# STM32G473CET6_PINOUT.net
KiCad netlist of a schematic drawn in Altium Designer
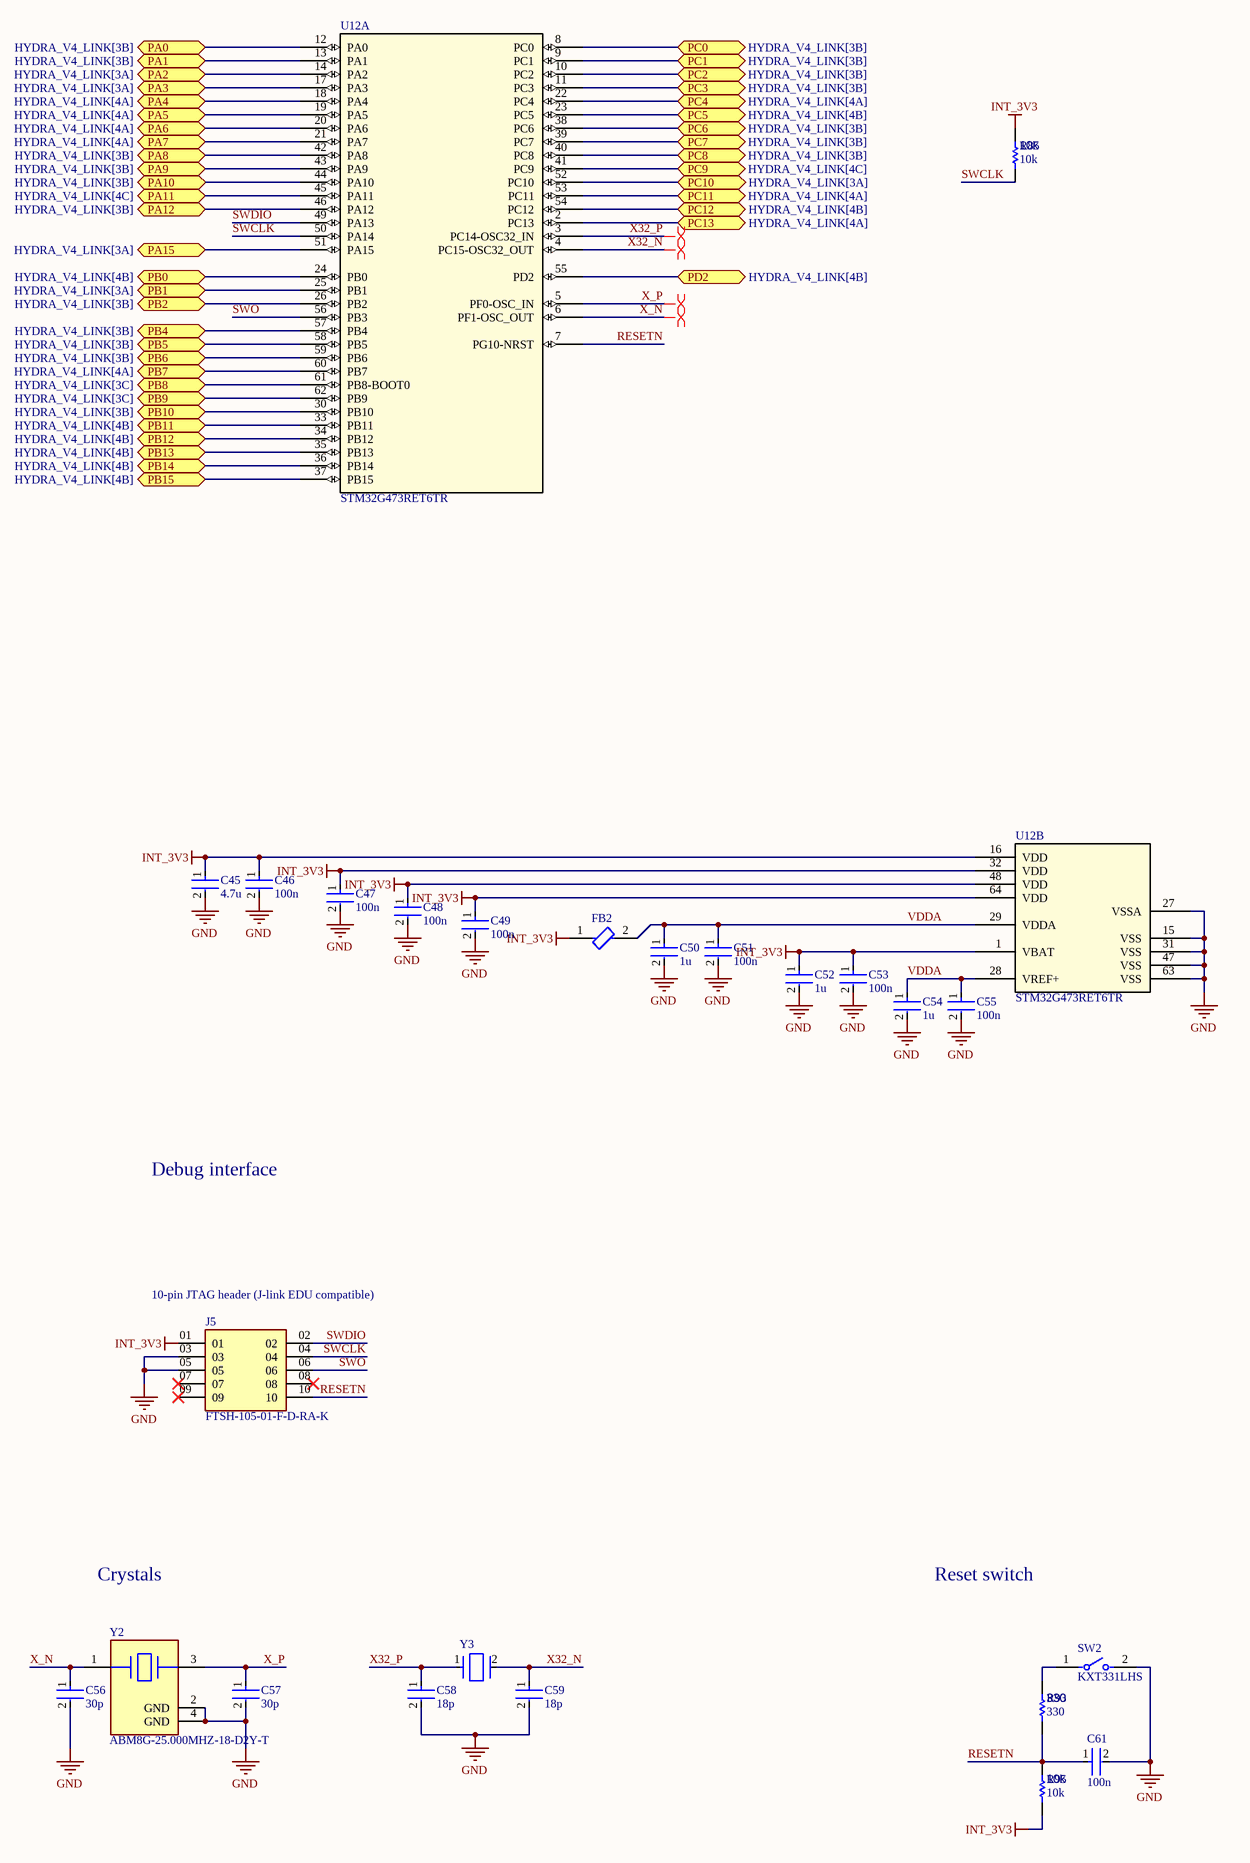
[diagram p0: STM32G473CET6_PINOUT.SchDoc]

(export (version "E")
  (design (tool "Eeschema 10.0.6"))
  (components
    (comp (ref "C45")
      (value "4.7u")
      (footprint "FP-0402-L_1_0_0_05-W_0_5-IPC_A")
      (description "LARGE PADS, 0402 CAP, CHANGE COMMENT TO MATCH REAL P/N")
      (libsource (lib "Space Concordia") (part "b4654b650e69147ec39a6b967a45e02"))
    )
    (comp (ref "C46")
      (value "100n")
      (footprint "FP-0402-L_1_0_0_05-W_0_5-IPC_A")
      (description "LARGE PADS, 0402 CAP, CHANGE COMMENT TO MATCH REAL P/N")
      (libsource (lib "Space Concordia") (part "b4654b650e69147ec39a6b967a45e02"))
    )
    (comp (ref "C47")
      (value "100n")
      (footprint "FP-0402-L_1_0_0_05-W_0_5-IPC_A")
      (description "LARGE PADS, 0402 CAP, CHANGE COMMENT TO MATCH REAL P/N")
      (libsource (lib "Space Concordia") (part "b4654b650e69147ec39a6b967a45e02"))
    )
    (comp (ref "C48")
      (value "100n")
      (footprint "FP-0402-L_1_0_0_05-W_0_5-IPC_A")
      (description "LARGE PADS, 0402 CAP, CHANGE COMMENT TO MATCH REAL P/N")
      (libsource (lib "Space Concordia") (part "b4654b650e69147ec39a6b967a45e02"))
    )
    (comp (ref "C49")
      (value "100n")
      (footprint "FP-0402-L_1_0_0_05-W_0_5-IPC_A")
      (description "LARGE PADS, 0402 CAP, CHANGE COMMENT TO MATCH REAL P/N")
      (libsource (lib "Space Concordia") (part "b4654b650e69147ec39a6b967a45e02"))
    )
    (comp (ref "C50")
      (value "1u")
      (footprint "FP-0402-L_1_0_0_05-W_0_5-IPC_A")
      (description "LARGE PADS, 0402 CAP, CHANGE COMMENT TO MATCH REAL P/N")
      (libsource (lib "Space Concordia") (part "b4654b650e69147ec39a6b967a45e02"))
    )
    (comp (ref "C51")
      (value "100n")
      (footprint "FP-0402-L_1_0_0_05-W_0_5-IPC_A")
      (description "LARGE PADS, 0402 CAP, CHANGE COMMENT TO MATCH REAL P/N")
      (libsource (lib "Space Concordia") (part "b4654b650e69147ec39a6b967a45e02"))
    )
    (comp (ref "C52")
      (value "1u")
      (footprint "FP-0402-L_1_0_0_05-W_0_5-IPC_A")
      (description "LARGE PADS, 0402 CAP, CHANGE COMMENT TO MATCH REAL P/N")
      (libsource (lib "Space Concordia") (part "b4654b650e69147ec39a6b967a45e02"))
    )
    (comp (ref "C53")
      (value "100n")
      (footprint "FP-0402-L_1_0_0_05-W_0_5-IPC_A")
      (description "LARGE PADS, 0402 CAP, CHANGE COMMENT TO MATCH REAL P/N")
      (libsource (lib "Space Concordia") (part "b4654b650e69147ec39a6b967a45e02"))
    )
    (comp (ref "C54")
      (value "1u")
      (footprint "FP-0402-L_1_0_0_05-W_0_5-IPC_A")
      (description "LARGE PADS, 0402 CAP, CHANGE COMMENT TO MATCH REAL P/N")
      (libsource (lib "Space Concordia") (part "b4654b650e69147ec39a6b967a45e02"))
    )
    (comp (ref "C55")
      (value "100n")
      (footprint "FP-0402-L_1_0_0_05-W_0_5-IPC_A")
      (description "LARGE PADS, 0402 CAP, CHANGE COMMENT TO MATCH REAL P/N")
      (libsource (lib "Space Concordia") (part "b4654b650e69147ec39a6b967a45e02"))
    )
    (comp (ref "C56")
      (value "30p")
      (footprint "FP-0402-L_1_0_0_05-W_0_5-IPC_A")
      (description "LARGE PADS, 0402 CAP, CHANGE COMMENT TO MATCH REAL P/N")
      (libsource (lib "Space Concordia") (part "b4654b650e69147ec39a6b967a45e02"))
    )
    (comp (ref "C57")
      (value "30p")
      (footprint "FP-0402-L_1_0_0_05-W_0_5-IPC_A")
      (description "LARGE PADS, 0402 CAP, CHANGE COMMENT TO MATCH REAL P/N")
      (libsource (lib "Space Concordia") (part "b4654b650e69147ec39a6b967a45e02"))
    )
    (comp (ref "C58")
      (value "18p")
      (footprint "FP-0402-L_1_0_0_05-W_0_5-IPC_A")
      (description "LARGE PADS, 0402 CAP, CHANGE COMMENT TO MATCH REAL P/N")
      (libsource (lib "Space Concordia") (part "b4654b650e69147ec39a6b967a45e02"))
    )
    (comp (ref "C59")
      (value "18p")
      (footprint "FP-0402-L_1_0_0_05-W_0_5-IPC_A")
      (description "LARGE PADS, 0402 CAP, CHANGE COMMENT TO MATCH REAL P/N")
      (libsource (lib "Space Concordia") (part "b4654b650e69147ec39a6b967a45e02"))
    )
    (comp (ref "C61")
      (value "100n")
      (footprint "FP-0402-L_1_0_0_05-W_0_5-IPC_A")
      (description "LARGE PADS, 0402 CAP, CHANGE COMMENT TO MATCH REAL P/N")
      (libsource (lib "Space Concordia") (part "b4654b650e69147ec39a6b967a45e02"))
    )
    (comp (ref "FB2")
      (value "BLM15PX601SN1D")
      (footprint "FP-BLM15-0_05-MFG")
      (description "Chip Ferrite Bead, 0402, 600Ω @ 100MHz, 0.23Ω, 25%, 900mA")
      (fields (field (name "TOLERANCE") "25%"))
      (libsource (lib "Altium Content Vault") (part "5f30dd21d616792df468990f7003faa"))
    )
    (comp (ref "J5")
      (value "FTSH-105-01-F-D-RA-K")
      (footprint "FTSH-105-01-F-D-RA-K-Footprint-1")
      (libsource (lib "Space Concordia") (part "FTSH-105-01-F-D-RA-K-Symbol-1"))
    )
    (comp (ref "R85")
      (value "10k")
      (footprint "R0603B")
      (description "Resistor")
      (fields (field (name "ALTIUM_VALUE") "10k"))
      (libsource (lib "Space Concordia") (part "Resistor"))
    )
    (comp (ref "R93")
      (value "330")
      (footprint "R0603B")
      (description "Resistor")
      (fields (field (name "ALTIUM_VALUE") "330"))
      (libsource (lib "Space Concordia") (part "Resistor"))
    )
    (comp (ref "R95")
      (value "10k")
      (footprint "R0603B")
      (description "Resistor")
      (fields (field (name "ALTIUM_VALUE") "10k"))
      (libsource (lib "Space Concordia") (part "Resistor"))
    )
    (comp (ref "SW2")
      (value "KXT331LHS")
      (footprint "FP-KXT331LHS-MFG")
      (description "SWITCH TACTILE SPST-NO 0.02A 15V")
      (libsource (lib "Altium Content Vault") (part "bb27bde45df87f1f469753f287ef5ae"))
    )
    (comp (ref "U12")
      (value "STM32G473RET6TR")
      (footprint "STM32G473RET6TR-Footprint-1")
      (description "MCU 32-Bit STM32 ARM Cortex-M4 RISC 512KB Flash 1.71V to 3.6V 64-Pin LQFP T/R")
      (libsource (lib "Space Concordia") (part "STM32G473RET6TR"))
    )
    (comp (ref "Y2")
      (value "ABM8G-25.000MHZ-18-D2Y-T")
      (footprint "FP-ABM8G-MFG")
      (description "Crystal 25MHz ±20ppm (Tol) ±30ppm (Stability) 18pF FUND 60Ω 4-Pin SMD T/R")
      (fields (field (name "TOLERANCE") "20ppm"))
      (libsource (lib "Altium Content Vault") (part "48e526d86b7f2615d98721063c72f49"))
    )
    (comp (ref "Y3")
      (value "ECS-.327-12.5-1210-TR")
      (footprint "FP-ECX-1210-MFG")
      (description "CRYSTAL 32.7680KHZ 12.5PF SMD")
      (fields
        (field (name "OCTOPART") "https://octopart.com/ecs-.327-12.5-1210-tr-ecs+international-81221340")
        (field (name "TOLERANCE") "20ppm")
      )
      (libsource (lib "Altium Content Vault") (part "99724985039315a44fd0d1401b84e49"))
    )
  )
  (nets
    (net (code "1") (name "/PA0") (class "Default")
      (node (ref "U12") (pin "12") (pinfunction "PA0_12") (pintype "bidirectional"))
    )
    (net (code "2") (name "/PA1") (class "Default")
      (node (ref "U12") (pin "13") (pinfunction "PA1_13") (pintype "bidirectional"))
    )
    (net (code "3") (name "/PA2") (class "Default")
      (node (ref "U12") (pin "14") (pinfunction "PA2_14") (pintype "bidirectional"))
    )
    (net (code "4") (name "/PA3") (class "Default")
      (node (ref "U12") (pin "17") (pinfunction "PA3_17") (pintype "bidirectional"))
    )
    (net (code "5") (name "/PA4") (class "Default")
      (node (ref "U12") (pin "18") (pinfunction "PA4_18") (pintype "bidirectional"))
    )
    (net (code "6") (name "/PA5") (class "Default")
      (node (ref "U12") (pin "19") (pinfunction "PA5_19") (pintype "bidirectional"))
    )
    (net (code "7") (name "/PA6") (class "Default")
      (node (ref "U12") (pin "20") (pinfunction "PA6_20") (pintype "bidirectional"))
    )
    (net (code "8") (name "/PA7") (class "Default")
      (node (ref "U12") (pin "21") (pinfunction "PA7_21") (pintype "bidirectional"))
    )
    (net (code "9") (name "/PA8") (class "Default")
      (node (ref "U12") (pin "42") (pinfunction "PA8_42") (pintype "bidirectional"))
    )
    (net (code "10") (name "/PA9") (class "Default")
      (node (ref "U12") (pin "43") (pinfunction "PA9_43") (pintype "bidirectional"))
    )
    (net (code "11") (name "/PA10") (class "Default")
      (node (ref "U12") (pin "44") (pinfunction "PA10_44") (pintype "bidirectional"))
    )
    (net (code "12") (name "/PA11") (class "Default")
      (node (ref "U12") (pin "45") (pinfunction "PA11_45") (pintype "bidirectional"))
    )
    (net (code "13") (name "/PA12") (class "Default")
      (node (ref "U12") (pin "46") (pinfunction "PA12_46") (pintype "bidirectional"))
    )
    (net (code "14") (name "/PA15") (class "Default")
      (node (ref "U12") (pin "51") (pinfunction "PA15_51") (pintype "bidirectional"))
    )
    (net (code "15") (name "/PB0") (class "Default")
      (node (ref "U12") (pin "24") (pinfunction "PB0_24") (pintype "bidirectional"))
    )
    (net (code "16") (name "/PB1") (class "Default")
      (node (ref "U12") (pin "25") (pinfunction "PB1_25") (pintype "bidirectional"))
    )
    (net (code "17") (name "/PB2") (class "Default")
      (node (ref "U12") (pin "26") (pinfunction "PB2_26") (pintype "bidirectional"))
    )
    (net (code "18") (name "/PB4") (class "Default")
      (node (ref "U12") (pin "57") (pinfunction "PB4_57") (pintype "bidirectional"))
    )
    (net (code "19") (name "/PB5") (class "Default")
      (node (ref "U12") (pin "58") (pinfunction "PB5_58") (pintype "bidirectional"))
    )
    (net (code "20") (name "/PB6") (class "Default")
      (node (ref "U12") (pin "59") (pinfunction "PB6_59") (pintype "bidirectional"))
    )
    (net (code "21") (name "/PB7") (class "Default")
      (node (ref "U12") (pin "60") (pinfunction "PB7_60") (pintype "bidirectional"))
    )
    (net (code "22") (name "/PB8") (class "Default")
      (node (ref "U12") (pin "61") (pinfunction "PB8-BOOT0_61") (pintype "bidirectional"))
    )
    (net (code "23") (name "/PB9") (class "Default")
      (node (ref "U12") (pin "62") (pinfunction "PB9_62") (pintype "bidirectional"))
    )
    (net (code "24") (name "/PB10") (class "Default")
      (node (ref "U12") (pin "30") (pinfunction "PB10_30") (pintype "bidirectional"))
    )
    (net (code "25") (name "/PB11") (class "Default")
      (node (ref "U12") (pin "33") (pinfunction "PB11_33") (pintype "bidirectional"))
    )
    (net (code "26") (name "/PB12") (class "Default")
      (node (ref "U12") (pin "34") (pinfunction "PB12_34") (pintype "bidirectional"))
    )
    (net (code "27") (name "/PB13") (class "Default")
      (node (ref "U12") (pin "35") (pinfunction "PB13_35") (pintype "bidirectional"))
    )
    (net (code "28") (name "/PB14") (class "Default")
      (node (ref "U12") (pin "36") (pinfunction "PB14_36") (pintype "bidirectional"))
    )
    (net (code "29") (name "/PB15") (class "Default")
      (node (ref "U12") (pin "37") (pinfunction "PB15_37") (pintype "bidirectional"))
    )
    (net (code "30") (name "/PC0") (class "Default")
      (node (ref "U12") (pin "8") (pinfunction "PC0_8") (pintype "bidirectional"))
    )
    (net (code "31") (name "/PC1") (class "Default")
      (node (ref "U12") (pin "9") (pinfunction "PC1_9") (pintype "bidirectional"))
    )
    (net (code "32") (name "/PC2") (class "Default")
      (node (ref "U12") (pin "10") (pinfunction "PC2_10") (pintype "bidirectional"))
    )
    (net (code "33") (name "/PC3") (class "Default")
      (node (ref "U12") (pin "11") (pinfunction "PC3_11") (pintype "bidirectional"))
    )
    (net (code "34") (name "/PC4") (class "Default")
      (node (ref "U12") (pin "22") (pinfunction "PC4_22") (pintype "bidirectional"))
    )
    (net (code "35") (name "/PC5") (class "Default")
      (node (ref "U12") (pin "23") (pinfunction "PC5_23") (pintype "bidirectional"))
    )
    (net (code "36") (name "/PC6") (class "Default")
      (node (ref "U12") (pin "38") (pinfunction "PC6_38") (pintype "bidirectional"))
    )
    (net (code "37") (name "/PC7") (class "Default")
      (node (ref "U12") (pin "39") (pinfunction "PC7_39") (pintype "bidirectional"))
    )
    (net (code "38") (name "/PC8") (class "Default")
      (node (ref "U12") (pin "40") (pinfunction "PC8_40") (pintype "bidirectional"))
    )
    (net (code "39") (name "/PC9") (class "Default")
      (node (ref "U12") (pin "41") (pinfunction "PC9_41") (pintype "bidirectional"))
    )
    (net (code "40") (name "/PC10") (class "Default")
      (node (ref "U12") (pin "52") (pinfunction "PC10_52") (pintype "bidirectional"))
    )
    (net (code "41") (name "/PC11") (class "Default")
      (node (ref "U12") (pin "53") (pinfunction "PC11_53") (pintype "bidirectional"))
    )
    (net (code "42") (name "/PC12") (class "Default")
      (node (ref "U12") (pin "54") (pinfunction "PC12_54") (pintype "bidirectional"))
    )
    (net (code "43") (name "/PC13") (class "Default")
      (node (ref "U12") (pin "2") (pinfunction "PC13_2") (pintype "bidirectional"))
    )
    (net (code "44") (name "/PD2") (class "Default")
      (node (ref "U12") (pin "55") (pinfunction "PD2_55") (pintype "bidirectional"))
    )
    (net (code "45") (name "/RESETN") (class "Default")
      (node (ref "C61") (pin "1") (pinfunction "1_1") (pintype "passive"))
      (node (ref "J5") (pin "10") (pinfunction "10_10") (pintype "passive"))
      (node (ref "R93") (pin "1") (pinfunction "1_1") (pintype "passive"))
      (node (ref "R95") (pin "2") (pinfunction "2_2") (pintype "passive"))
      (node (ref "U12") (pin "7") (pinfunction "PG10-NRST_7") (pintype "bidirectional"))
    )
    (net (code "46") (name "/SWCLK") (class "Default")
      (node (ref "J5") (pin "04") (pinfunction "04_04") (pintype "passive"))
      (node (ref "R85") (pin "1") (pinfunction "1_1") (pintype "passive"))
      (node (ref "U12") (pin "50") (pinfunction "PA14_50") (pintype "bidirectional"))
    )
    (net (code "47") (name "/SWDIO") (class "Default")
      (node (ref "J5") (pin "02") (pinfunction "02_02") (pintype "passive"))
      (node (ref "U12") (pin "49") (pinfunction "PA13_49") (pintype "bidirectional"))
    )
    (net (code "48") (name "/SWO") (class "Default")
      (node (ref "J5") (pin "06") (pinfunction "06_06") (pintype "passive"))
      (node (ref "U12") (pin "56") (pinfunction "PB3_56") (pintype "bidirectional"))
    )
    (net (code "49") (name "/VDDA") (class "Default")
      (node (ref "C50") (pin "1") (pinfunction "1_1") (pintype "passive"))
      (node (ref "C51") (pin "1") (pinfunction "1_1") (pintype "passive"))
      (node (ref "C54") (pin "1") (pinfunction "1_1") (pintype "passive"))
      (node (ref "C55") (pin "1") (pinfunction "1_1") (pintype "passive"))
      (node (ref "FB2") (pin "2") (pinfunction "2_2") (pintype "passive"))
      (node (ref "U12") (pin "28") (pinfunction "VREF+_28") (pintype "power_in"))
      (node (ref "U12") (pin "29") (pinfunction "VDDA_29") (pintype "power_in"))
    )
    (net (code "50") (name "/X32_N") (class "Default")
      (node (ref "C59") (pin "1") (pinfunction "1_1") (pintype "passive"))
      (node (ref "U12") (pin "4") (pinfunction "PC15-OSC32_OUT_4") (pintype "bidirectional"))
      (node (ref "Y3") (pin "2") (pinfunction "Out/In_2") (pintype "passive"))
    )
    (net (code "51") (name "/X32_P") (class "Default")
      (node (ref "C58") (pin "1") (pinfunction "1_1") (pintype "passive"))
      (node (ref "U12") (pin "3") (pinfunction "PC14-OSC32_IN_3") (pintype "bidirectional"))
      (node (ref "Y3") (pin "1") (pinfunction "In/Out_1") (pintype "passive"))
    )
    (net (code "52") (name "/X_N") (class "Default")
      (node (ref "C56") (pin "1") (pinfunction "1_1") (pintype "passive"))
      (node (ref "U12") (pin "6") (pinfunction "PF1-OSC_OUT_6") (pintype "bidirectional"))
      (node (ref "Y2") (pin "1") (pinfunction "1_1") (pintype "passive"))
    )
    (net (code "53") (name "/X_P") (class "Default")
      (node (ref "C57") (pin "1") (pinfunction "1_1") (pintype "passive"))
      (node (ref "U12") (pin "5") (pinfunction "PF0-OSC_IN_5") (pintype "bidirectional"))
      (node (ref "Y2") (pin "3") (pinfunction "3_3") (pintype "passive"))
    )
    (net (code "54") (name "GND") (class "Default")
      (node (ref "C45") (pin "2") (pinfunction "2_2") (pintype "passive"))
      (node (ref "C46") (pin "2") (pinfunction "2_2") (pintype "passive"))
      (node (ref "C47") (pin "2") (pinfunction "2_2") (pintype "passive"))
      (node (ref "C48") (pin "2") (pinfunction "2_2") (pintype "passive"))
      (node (ref "C49") (pin "2") (pinfunction "2_2") (pintype "passive"))
      (node (ref "C50") (pin "2") (pinfunction "2_2") (pintype "passive"))
      (node (ref "C51") (pin "2") (pinfunction "2_2") (pintype "passive"))
      (node (ref "C52") (pin "2") (pinfunction "2_2") (pintype "passive"))
      (node (ref "C53") (pin "2") (pinfunction "2_2") (pintype "passive"))
      (node (ref "C54") (pin "2") (pinfunction "2_2") (pintype "passive"))
      (node (ref "C55") (pin "2") (pinfunction "2_2") (pintype "passive"))
      (node (ref "C56") (pin "2") (pinfunction "2_2") (pintype "passive"))
      (node (ref "C57") (pin "2") (pinfunction "2_2") (pintype "passive"))
      (node (ref "C58") (pin "2") (pinfunction "2_2") (pintype "passive"))
      (node (ref "C59") (pin "2") (pinfunction "2_2") (pintype "passive"))
      (node (ref "C61") (pin "2") (pinfunction "2_2") (pintype "passive"))
      (node (ref "J5") (pin "03") (pinfunction "03_03") (pintype "passive"))
      (node (ref "J5") (pin "05") (pinfunction "05_05") (pintype "passive"))
      (node (ref "SW2") (pin "2") (pinfunction "2_2") (pintype "passive"))
      (node (ref "U12") (pin "15") (pinfunction "VSS_15") (pintype "power_in"))
      (node (ref "U12") (pin "27") (pinfunction "VSSA_27") (pintype "power_in"))
      (node (ref "U12") (pin "31") (pinfunction "VSS_31") (pintype "power_in"))
      (node (ref "U12") (pin "47") (pinfunction "VSS_47") (pintype "power_in"))
      (node (ref "U12") (pin "63") (pinfunction "VSS_63") (pintype "power_in"))
      (node (ref "Y2") (pin "2") (pinfunction "GND_2") (pintype "power_in"))
      (node (ref "Y2") (pin "4") (pinfunction "GND_4") (pintype "power_in"))
    )
    (net (code "55") (name "INT_3V3") (class "Default")
      (node (ref "C45") (pin "1") (pinfunction "1_1") (pintype "passive"))
      (node (ref "C46") (pin "1") (pinfunction "1_1") (pintype "passive"))
      (node (ref "C47") (pin "1") (pinfunction "1_1") (pintype "passive"))
      (node (ref "C48") (pin "1") (pinfunction "1_1") (pintype "passive"))
      (node (ref "C49") (pin "1") (pinfunction "1_1") (pintype "passive"))
      (node (ref "C52") (pin "1") (pinfunction "1_1") (pintype "passive"))
      (node (ref "C53") (pin "1") (pinfunction "1_1") (pintype "passive"))
      (node (ref "FB2") (pin "1") (pinfunction "1_1") (pintype "passive"))
      (node (ref "J5") (pin "01") (pinfunction "01_01") (pintype "passive"))
      (node (ref "R85") (pin "2") (pinfunction "2_2") (pintype "passive"))
      (node (ref "R95") (pin "1") (pinfunction "1_1") (pintype "passive"))
      (node (ref "U12") (pin "1") (pinfunction "VBAT_1") (pintype "power_in"))
      (node (ref "U12") (pin "16") (pinfunction "VDD_16") (pintype "power_in"))
      (node (ref "U12") (pin "32") (pinfunction "VDD_32") (pintype "power_in"))
      (node (ref "U12") (pin "48") (pinfunction "VDD_48") (pintype "power_in"))
      (node (ref "U12") (pin "64") (pinfunction "VDD_64") (pintype "power_in"))
    )
    (net (code "56") (name "Net-(R93-Pad2)") (class "Default")
      (node (ref "R93") (pin "2") (pinfunction "2_2") (pintype "passive"))
      (node (ref "SW2") (pin "1") (pinfunction "1_1") (pintype "passive"))
    )
    (net (code "57") (name "unconnected-(J5-Pad07)") (class "Default")
      (node (ref "J5") (pin "07") (pinfunction "07_07") (pintype "passive+no_connect"))
    )
    (net (code "58") (name "unconnected-(J5-Pad08)") (class "Default")
      (node (ref "J5") (pin "08") (pinfunction "08_08") (pintype "passive+no_connect"))
    )
    (net (code "59") (name "unconnected-(J5-Pad09)") (class "Default")
      (node (ref "J5") (pin "09") (pinfunction "09_09") (pintype "passive+no_connect"))
    )
  )
)
